# LEO_COTS_rev0.net
KiCad netlist of a schematic drawn in Altium Designer
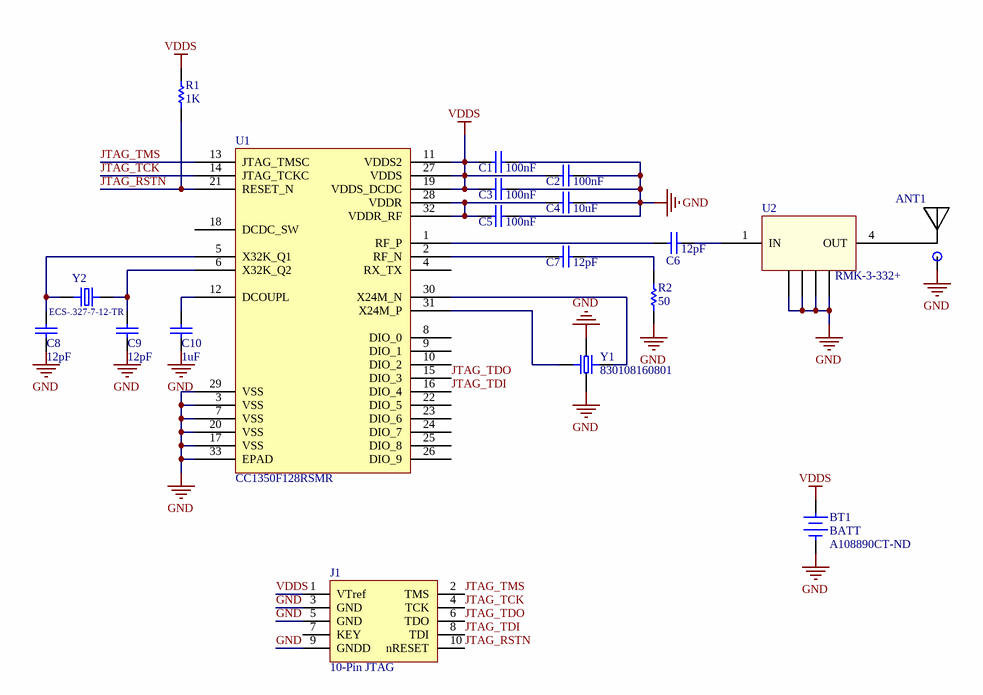
[diagram p0: LEO_COTS_rev0.SchDoc]

(export (version "E")
  (design (tool "Eeschema 10.0.6"))
  (components
    (comp (ref "ANT1")
      (value "ANT")
      (footprint "RESLOOP_OD10_fw15_fl180_sw12_sl15")
      (libsource (lib "LEO_COTS_components") (part "ANT"))
    )
    (comp (ref "BT1")
      (value "BATT")
      (footprint "1318164-1")
      (fields (field (name "SUPPLIER PART NUMBER 1") "A108890CT-ND"))
      (libsource (lib "LEO_COTS_components") (part "BATT"))
    )
    (comp (ref "C1")
      (value "100nF")
      (footprint "CAPC0603X04N")
      (description "CAP CER 0201")
      (fields (field (name "Comment") "CAP_0201"))
      (libsource (lib "LEO_COTS_components") (part "CAP_0201"))
    )
    (comp (ref "C2")
      (value "100nF")
      (footprint "CAPC0603X04N")
      (description "CAP CER 0201")
      (fields (field (name "Comment") "CAP_0201"))
      (libsource (lib "LEO_COTS_components") (part "CAP_0201"))
    )
    (comp (ref "C3")
      (value "100nF")
      (footprint "CAPC0603X04N")
      (description "CAP CER 0201")
      (fields (field (name "Comment") "CAP_0201"))
      (libsource (lib "LEO_COTS_components") (part "CAP_0201"))
    )
    (comp (ref "C4")
      (value "10uF")
      (footprint "CAPC1608X05N")
      (description "CAP CER 0603")
      (fields (field (name "Comment") "CAP_0603"))
      (libsource (lib "LEO_COTS_components") (part "CAP_0603"))
    )
    (comp (ref "C5")
      (value "100nF")
      (footprint "CAPC0603X04N")
      (description "CAP CER 0201")
      (fields (field (name "Comment") "CAP_0201"))
      (libsource (lib "LEO_COTS_components") (part "CAP_0201"))
    )
    (comp (ref "C6")
      (value "12pF")
      (footprint "1608[0603]")
      (description "CAP CER 0603")
      (fields (field (name "Comment") "CAP"))
      (libsource (lib "LEO_COTS_components") (part "CAP"))
    )
    (comp (ref "C7")
      (value "12pF")
      (footprint "CAPC0603X04N")
      (description "CAP CER 0201")
      (fields (field (name "Comment") "CAP_0201"))
      (libsource (lib "LEO_COTS_components") (part "CAP_0201"))
    )
    (comp (ref "C8")
      (value "12pF")
      (footprint "CAPC0603X04N")
      (description "CAP CER 0201")
      (fields (field (name "Comment") "CAP_0201"))
      (libsource (lib "LEO_COTS_components") (part "CAP_0201"))
    )
    (comp (ref "C9")
      (value "12pF")
      (footprint "CAPC0603X04N")
      (description "CAP CER 0201")
      (fields (field (name "Comment") "CAP_0201"))
      (libsource (lib "LEO_COTS_components") (part "CAP_0201"))
    )
    (comp (ref "C10")
      (value "1uF")
      (footprint "CAPC0603X04N")
      (description "CAP CER 0201")
      (fields (field (name "Comment") "CAP_0201"))
      (libsource (lib "LEO_COTS_components") (part "CAP_0201"))
    )
    (comp (ref "J1")
      (value "10-Pin JTAG")
      (footprint "FTSH-105-01-F-DV-007-K")
      (libsource (lib "LEO_COTS_components") (part "CM10"))
    )
    (comp (ref "R1")
      (value "1K")
      (footprint "CAPC0603X04N")
      (description "Semiconductor Resistor")
      (fields (field (name "Comment") "Res Semi") (field (name "PUBLISHER") "Altium Limited"))
      (libsource (lib "LEO_COTS_components") (part "Res Semi"))
    )
    (comp (ref "R2")
      (value "50")
      (footprint "CAPC0603X04N")
      (description "Semiconductor Resistor")
      (fields (field (name "Comment") "Res Semi") (field (name "PUBLISHER") "Altium Limited"))
      (libsource (lib "LEO_COTS_components") (part "Res Semi"))
    )
    (comp (ref "U1")
      (value "CC1350F128RSMR")
      (footprint "QFN40P400X400X100-33N")
      (description "Ultra-Low-Power Dual-Band Wireless MCU")
      (libsource (lib "LEO_COTS_components") (part "CC1350F128RSMR"))
    )
    (comp (ref "U2")
      (value "RMK-3-332+")
      (footprint "RMK-3-331+")
      (description "3x Frequency Multiplier")
      (libsource (lib "LEO_COTS_components") (part "RMK-3-332+"))
    )
    (comp (ref "Y1")
      (value "830108160801")
      (footprint "LFXTAL081608")
      (description "24 MHz crystal")
      (fields (field (name "MP") "ECS-.327-7-12-TR"))
      (libsource (lib "LEO_COTS_components") (part "830108160801"))
    )
    (comp (ref "Y2")
      (value "ECS-.327-7-12-TR")
      (footprint "XTAL_ECS-.327-7-12-TR")
      (description "32.768 kHz SMD Crystal")
      (libsource (lib "LEO_COTS_components") (part "ECS-.327-7-12-TR"))
    )
  )
  (nets
    (net (code "1") (name "/JTAG_RSTN") (class "Default")
      (node (ref "J1") (pin "10") (pinfunction "nRESET_10") (pintype "passive"))
      (node (ref "R1") (pin "1") (pinfunction "1_1") (pintype "passive"))
      (node (ref "U1") (pin "21") (pinfunction "RESET_N_21") (pintype "passive"))
    )
    (net (code "2") (name "/JTAG_TCK") (class "Default")
      (node (ref "J1") (pin "4") (pinfunction "TCK_4") (pintype "passive"))
      (node (ref "U1") (pin "14") (pinfunction "JTAG_TCKC_14") (pintype "passive"))
    )
    (net (code "3") (name "/JTAG_TDI") (class "Default")
      (node (ref "J1") (pin "8") (pinfunction "TDI_8") (pintype "passive"))
      (node (ref "U1") (pin "16") (pinfunction "DIO_4_16") (pintype "passive"))
    )
    (net (code "4") (name "/JTAG_TDO") (class "Default")
      (node (ref "J1") (pin "6") (pinfunction "TDO_6") (pintype "passive"))
      (node (ref "U1") (pin "15") (pinfunction "DIO_3_15") (pintype "passive"))
    )
    (net (code "5") (name "/JTAG_TMS") (class "Default")
      (node (ref "J1") (pin "2") (pinfunction "TMS_2") (pintype "passive"))
      (node (ref "U1") (pin "13") (pinfunction "JTAG_TMSC_13") (pintype "passive"))
    )
    (net (code "6") (name "GND") (class "Default")
      (node (ref "ANT1") (pin "2") (pinfunction "-_2") (pintype "passive"))
      (node (ref "BT1") (pin "2") (pinfunction "-_2") (pintype "passive"))
      (node (ref "C1") (pin "1") (pinfunction "1_1") (pintype "passive"))
      (node (ref "C10") (pin "1") (pinfunction "1_1") (pintype "passive"))
      (node (ref "C2") (pin "1") (pinfunction "1_1") (pintype "passive"))
      (node (ref "C3") (pin "1") (pinfunction "1_1") (pintype "passive"))
      (node (ref "C4") (pin "2") (pinfunction "2_2") (pintype "passive"))
      (node (ref "C5") (pin "1") (pinfunction "1_1") (pintype "passive"))
      (node (ref "C8") (pin "1") (pinfunction "1_1") (pintype "passive"))
      (node (ref "C9") (pin "1") (pinfunction "1_1") (pintype "passive"))
      (node (ref "J1") (pin "3") (pinfunction "GND_3") (pintype "passive"))
      (node (ref "J1") (pin "5") (pinfunction "GND_5") (pintype "passive"))
      (node (ref "J1") (pin "9") (pinfunction "GNDD_9") (pintype "passive"))
      (node (ref "R2") (pin "1") (pinfunction "1_1") (pintype "passive"))
      (node (ref "U1") (pin "17") (pinfunction "VSS_17") (pintype "passive"))
      (node (ref "U1") (pin "20") (pinfunction "VSS_20") (pintype "passive"))
      (node (ref "U1") (pin "29") (pinfunction "VSS_29") (pintype "passive"))
      (node (ref "U1") (pin "3") (pinfunction "VSS_3") (pintype "passive"))
      (node (ref "U1") (pin "33") (pinfunction "EPAD_33") (pintype "passive"))
      (node (ref "U1") (pin "7") (pinfunction "VSS_7") (pintype "passive"))
      (node (ref "U2") (pin "2") (pinfunction "2_2") (pintype "passive"))
      (node (ref "U2") (pin "3") (pinfunction "3_3") (pintype "passive"))
      (node (ref "U2") (pin "5") (pinfunction "5_5") (pintype "passive"))
      (node (ref "U2") (pin "6") (pinfunction "6_6") (pintype "passive"))
      (node (ref "Y1") (pin "2") (pinfunction "2_2") (pintype "passive"))
      (node (ref "Y1") (pin "4") (pinfunction "4_4") (pintype "passive"))
    )
    (net (code "7") (name "Net-(ANT1-+)") (class "Default")
      (node (ref "ANT1") (pin "1") (pinfunction "+_1") (pintype "passive"))
      (node (ref "U2") (pin "4") (pinfunction "OUT_4") (pintype "passive"))
    )
    (net (code "8") (name "Net-(C7-Pad1)") (class "Default")
      (node (ref "C7") (pin "1") (pinfunction "1_1") (pintype "passive"))
      (node (ref "R2") (pin "2") (pinfunction "2_2") (pintype "passive"))
    )
    (net (code "9") (name "Net-(U1-DCOUPL)") (class "Default")
      (node (ref "C10") (pin "2") (pinfunction "2_2") (pintype "passive"))
      (node (ref "U1") (pin "12") (pinfunction "DCOUPL_12") (pintype "passive"))
    )
    (net (code "10") (name "Net-(U1-RF_N)") (class "Default")
      (node (ref "C7") (pin "2") (pinfunction "2_2") (pintype "passive"))
      (node (ref "U1") (pin "2") (pinfunction "RF_N_2") (pintype "passive"))
    )
    (net (code "11") (name "Net-(U1-RF_P)") (class "Default")
      (node (ref "C6") (pin "1") (pinfunction "1_1") (pintype "passive"))
      (node (ref "U1") (pin "1") (pinfunction "RF_P_1") (pintype "passive"))
    )
    (net (code "12") (name "Net-(U1-VDDR)") (class "Default")
      (node (ref "C4") (pin "1") (pinfunction "1_1") (pintype "passive"))
      (node (ref "C5") (pin "2") (pinfunction "2_2") (pintype "passive"))
      (node (ref "U1") (pin "28") (pinfunction "VDDR_28") (pintype "passive"))
      (node (ref "U1") (pin "32") (pinfunction "VDDR_RF_32") (pintype "passive"))
    )
    (net (code "13") (name "Net-(U1-X24M_N)") (class "Default")
      (node (ref "U1") (pin "30") (pinfunction "X24M_N_30") (pintype "passive"))
      (node (ref "Y1") (pin "3") (pinfunction "3_3") (pintype "passive"))
    )
    (net (code "14") (name "Net-(U1-X24M_P)") (class "Default")
      (node (ref "U1") (pin "31") (pinfunction "X24M_P_31") (pintype "passive"))
      (node (ref "Y1") (pin "1") (pinfunction "1_1") (pintype "passive"))
    )
    (net (code "15") (name "Net-(U1-X32K_Q1)") (class "Default")
      (node (ref "C8") (pin "2") (pinfunction "2_2") (pintype "passive"))
      (node (ref "U1") (pin "5") (pinfunction "X32K_Q1_5") (pintype "passive"))
      (node (ref "Y2") (pin "1") (pinfunction "1_1") (pintype "passive"))
    )
    (net (code "16") (name "Net-(U1-X32K_Q2)") (class "Default")
      (node (ref "C9") (pin "2") (pinfunction "2_2") (pintype "passive"))
      (node (ref "U1") (pin "6") (pinfunction "X32K_Q2_6") (pintype "passive"))
      (node (ref "Y2") (pin "2") (pinfunction "2_2") (pintype "passive"))
    )
    (net (code "17") (name "Net-(U2-IN)") (class "Default")
      (node (ref "C6") (pin "2") (pinfunction "2_2") (pintype "passive"))
      (node (ref "U2") (pin "1") (pinfunction "IN_1") (pintype "passive"))
    )
    (net (code "18") (name "VDDS") (class "Default")
      (node (ref "BT1") (pin "1") (pinfunction "+_1") (pintype "passive"))
      (node (ref "C1") (pin "2") (pinfunction "2_2") (pintype "passive"))
      (node (ref "C2") (pin "2") (pinfunction "2_2") (pintype "passive"))
      (node (ref "C3") (pin "2") (pinfunction "2_2") (pintype "passive"))
      (node (ref "J1") (pin "1") (pinfunction "VTref_1") (pintype "passive"))
      (node (ref "R1") (pin "2") (pinfunction "2_2") (pintype "passive"))
      (node (ref "U1") (pin "11") (pinfunction "VDDS2_11") (pintype "passive"))
      (node (ref "U1") (pin "19") (pinfunction "VDDS_DCDC_19") (pintype "passive"))
      (node (ref "U1") (pin "27") (pinfunction "VDDS_27") (pintype "passive"))
    )
    (net (code "19") (name "unconnected-(J1-KEY-Pad7)") (class "Default")
      (node (ref "J1") (pin "7") (pinfunction "KEY_7") (pintype "passive"))
    )
    (net (code "20") (name "unconnected-(U1-DCDC_SW-Pad18)") (class "Default")
      (node (ref "U1") (pin "18") (pinfunction "DCDC_SW_18") (pintype "passive"))
    )
    (net (code "21") (name "unconnected-(U1-DIO_0-Pad8)") (class "Default")
      (node (ref "U1") (pin "8") (pinfunction "DIO_0_8") (pintype "passive"))
    )
    (net (code "22") (name "unconnected-(U1-DIO_1-Pad9)") (class "Default")
      (node (ref "U1") (pin "9") (pinfunction "DIO_1_9") (pintype "passive"))
    )
    (net (code "23") (name "unconnected-(U1-DIO_2-Pad10)") (class "Default")
      (node (ref "U1") (pin "10") (pinfunction "DIO_2_10") (pintype "passive"))
    )
    (net (code "24") (name "unconnected-(U1-DIO_5-Pad22)") (class "Default")
      (node (ref "U1") (pin "22") (pinfunction "DIO_5_22") (pintype "passive"))
    )
    (net (code "25") (name "unconnected-(U1-DIO_6-Pad23)") (class "Default")
      (node (ref "U1") (pin "23") (pinfunction "DIO_6_23") (pintype "passive"))
    )
    (net (code "26") (name "unconnected-(U1-DIO_7-Pad24)") (class "Default")
      (node (ref "U1") (pin "24") (pinfunction "DIO_7_24") (pintype "passive"))
    )
    (net (code "27") (name "unconnected-(U1-DIO_8-Pad25)") (class "Default")
      (node (ref "U1") (pin "25") (pinfunction "DIO_8_25") (pintype "passive"))
    )
    (net (code "28") (name "unconnected-(U1-DIO_9-Pad26)") (class "Default")
      (node (ref "U1") (pin "26") (pinfunction "DIO_9_26") (pintype "passive"))
    )
    (net (code "29") (name "unconnected-(U1-RX_TX-Pad4)") (class "Default")
      (node (ref "U1") (pin "4") (pinfunction "RX_TX_4") (pintype "passive"))
    )
  )
)
